# power.net
KiCad netlist of a schematic drawn in Altium Designer
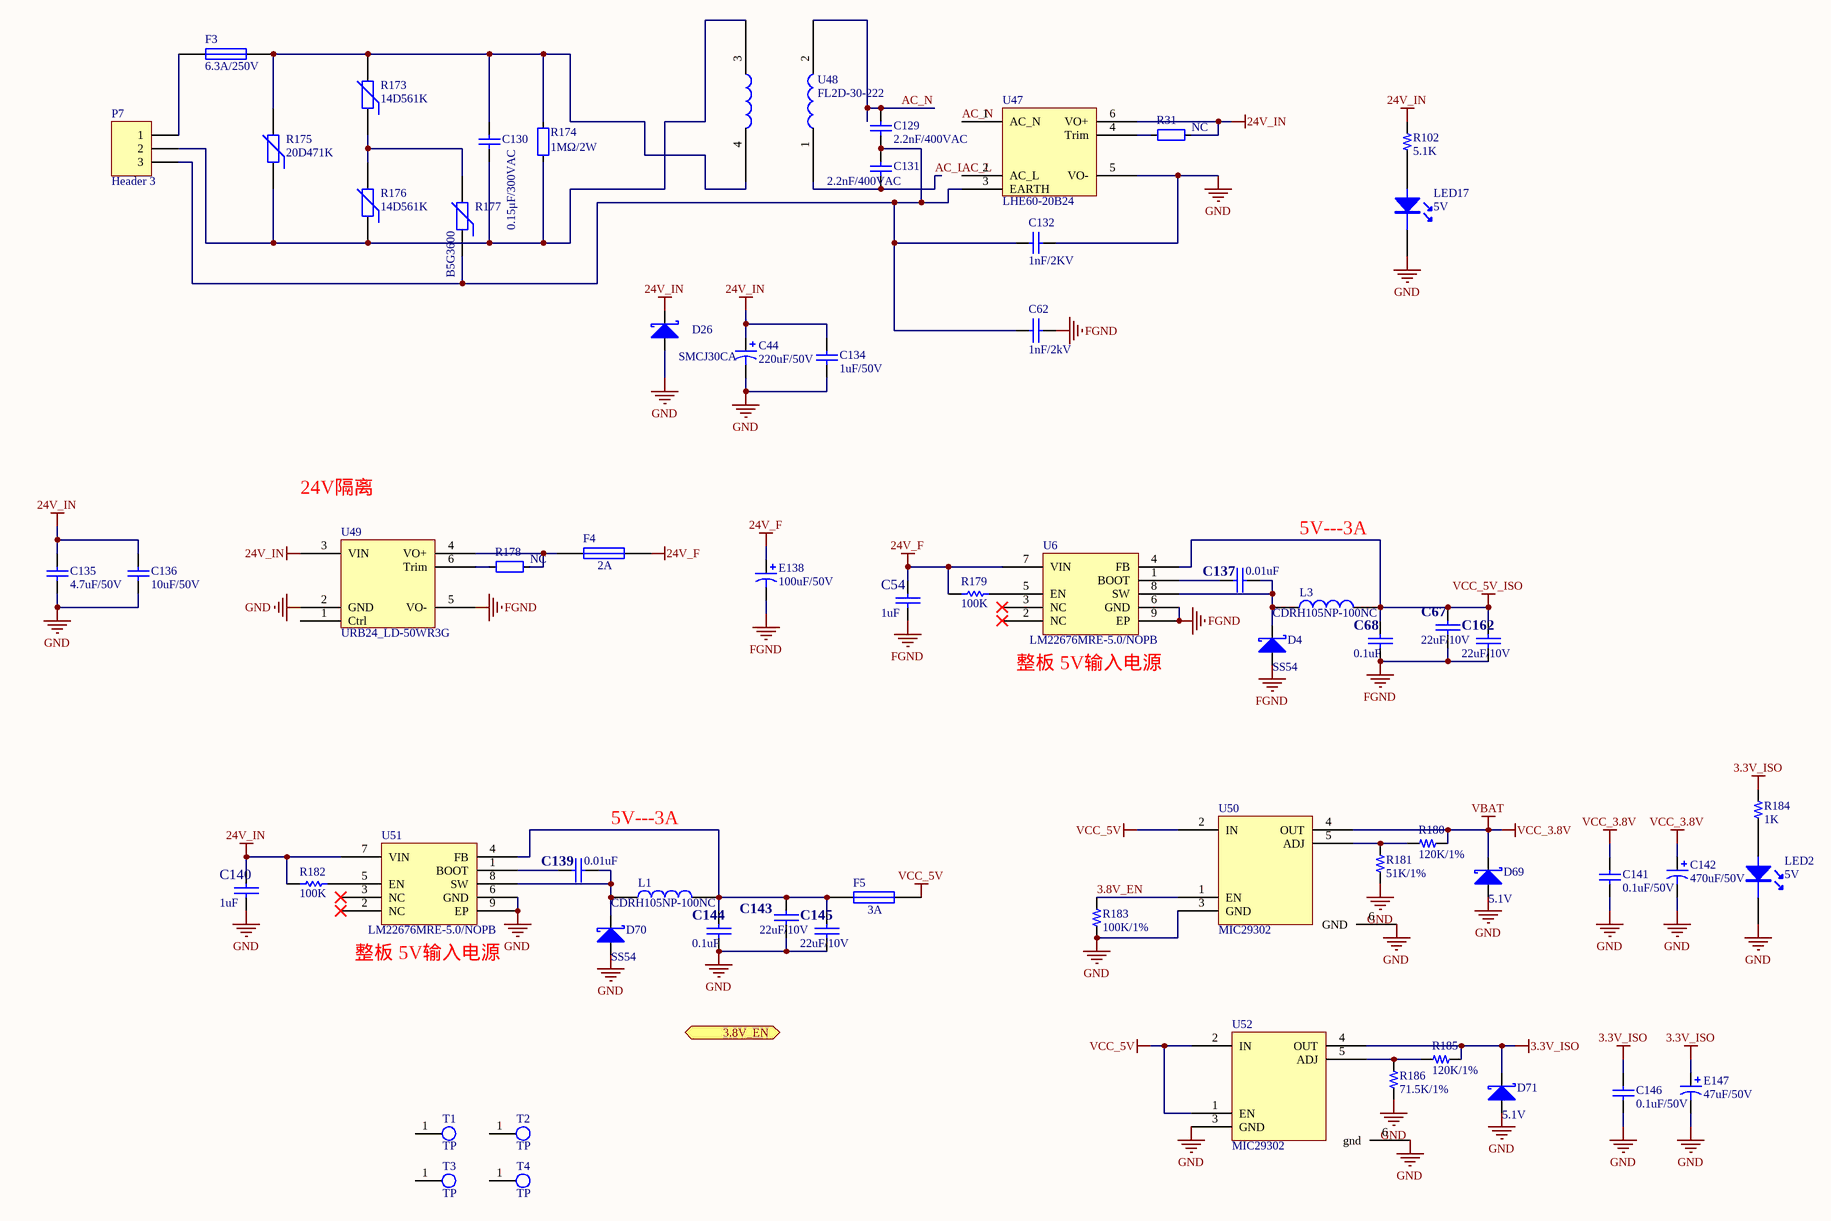
[diagram p0: power.SchDoc]

(export (version "E")
  (design (tool "Eeschema 10.0.6"))
  (components
    (comp (ref "C44")
      (value "220uF/50V")
      (footprint "Φ10×10")
      (description "Polarized Capacitor (Radial)")
      (fields (field (name "PUBLISHER") "Altium Limited"))
      (libsource (lib "Miscellaneous Devices") (part "Cap Pol1"))
    )
    (comp (ref "C54")
      (value "1uF")
      (footprint "0603C")
      (description "Capacitor")
      (libsource (lib "*") (part "CAP"))
    )
    (comp (ref "C62")
      (value "1nF/2kV")
      (footprint "1206C")
      (description "Capacitor")
      (libsource (lib "*") (part "CAP"))
    )
    (comp (ref "C67")
      (value "22uF/10V")
      (footprint "1210C")
      (description "Capacitor")
      (libsource (lib "*") (part "CAP"))
    )
    (comp (ref "C68")
      (value "0.1uF")
      (footprint "0603C")
      (description "Capacitor")
      (libsource (lib "*") (part "CAP"))
    )
    (comp (ref "C129")
      (value "2.2nF/400VAC")
      (footprint "15x18")
      (description "Capacitor")
      (fields (field (name "PUBLISHER") "Altium Limited"))
      (libsource (lib "Miscellaneous Devices") (part "Cap"))
    )
    (comp (ref "C130")
      (value "0.15μF/300VAC")
      (footprint "15x18")
      (description "Capacitor")
      (fields (field (name "PUBLISHER") "Altium Limited"))
      (libsource (lib "Miscellaneous Devices") (part "Cap"))
    )
    (comp (ref "C131")
      (value "2.2nF/400VAC")
      (footprint "15x18")
      (description "Capacitor")
      (fields (field (name "PUBLISHER") "Altium Limited"))
      (libsource (lib "Miscellaneous Devices") (part "Cap"))
    )
    (comp (ref "C132")
      (value "1nF/2KV")
      (footprint "1206C")
      (description "Capacitor")
      (fields (field (name "PUBLISHER") "Altium Limited"))
      (libsource (lib "Miscellaneous Devices") (part "Cap"))
    )
    (comp (ref "C134")
      (value "1uF/50V")
      (footprint "1210C")
      (description "Capacitor")
      (fields (field (name "PUBLISHER") "Altium Limited"))
      (libsource (lib "Miscellaneous Devices") (part "Cap"))
    )
    (comp (ref "C135")
      (value "4.7uF/50V")
      (footprint "1210C")
      (description "Capacitor")
      (fields (field (name "PUBLISHER") "Altium Limited"))
      (libsource (lib "Miscellaneous Devices") (part "Cap"))
    )
    (comp (ref "C136")
      (value "10uF/50V")
      (footprint "1210C")
      (description "Capacitor")
      (fields (field (name "PUBLISHER") "Altium Limited"))
      (libsource (lib "Miscellaneous Devices") (part "Cap"))
    )
    (comp (ref "C137")
      (value "0.01uF")
      (footprint "0603C")
      (description "Capacitor")
      (libsource (lib "*") (part "CAP"))
    )
    (comp (ref "C139")
      (value "0.01uF")
      (footprint "0603C")
      (description "Capacitor")
      (libsource (lib "*") (part "CAP"))
    )
    (comp (ref "C140")
      (value "1uF")
      (footprint "0603C")
      (description "Capacitor")
      (libsource (lib "*") (part "CAP"))
    )
    (comp (ref "C141")
      (value "0.1uF/50V")
      (footprint "0603C")
      (description "Capacitor")
      (fields (field (name "PUBLISHER") "Altium Limited"))
      (libsource (lib "Miscellaneous Devices") (part "Cap"))
    )
    (comp (ref "C142")
      (value "470uF/50V")
      (footprint "Φ10×10")
      (description "Polarized Capacitor (Radial)")
      (fields (field (name "PUBLISHER") "Altium Limited"))
      (libsource (lib "Miscellaneous Devices") (part "Cap Pol1"))
    )
    (comp (ref "C143")
      (value "22uF/10V")
      (footprint "1210C")
      (description "Capacitor")
      (libsource (lib "*") (part "CAP"))
    )
    (comp (ref "C144")
      (value "0.1uF")
      (footprint "0603C")
      (description "Capacitor")
      (libsource (lib "*") (part "CAP"))
    )
    (comp (ref "C145")
      (value "22uF/10V")
      (footprint "1210C")
      (description "Capacitor")
      (libsource (lib "*") (part "CAP"))
    )
    (comp (ref "C146")
      (value "0.1uF/50V")
      (footprint "0603C")
      (description "Capacitor")
      (fields (field (name "PUBLISHER") "Altium Limited"))
      (libsource (lib "Miscellaneous Devices") (part "Cap"))
    )
    (comp (ref "C162")
      (value "22uF/10V")
      (footprint "1210C")
      (description "Capacitor")
      (libsource (lib "*") (part "CAP"))
    )
    (comp (ref "D4")
      (value "SS54")
      (footprint "SMC")
      (description "Schottky Diode")
      (libsource (lib "*") (part "DIODE S"))
    )
    (comp (ref "D26")
      (value "SMCJ30CA")
      (footprint "SMC")
      (description "Schottky Diode")
      (libsource (lib "*") (part "DIODE S"))
    )
    (comp (ref "D69")
      (value "5.1V")
      (footprint "SMA")
      (description "Schottky Diode")
      (libsource (lib "*") (part "DIODE S"))
    )
    (comp (ref "D70")
      (value "SS54")
      (footprint "SMC")
      (description "Schottky Diode")
      (libsource (lib "*") (part "DIODE S"))
    )
    (comp (ref "D71")
      (value "5.1V")
      (footprint "SMA")
      (description "Schottky Diode")
      (libsource (lib "*") (part "DIODE S"))
    )
    (comp (ref "E138")
      (value "100uF/50V")
      (footprint "Φ10×10")
      (description "Polarized Capacitor (Radial)")
      (fields (field (name "PUBLISHER") "Altium Limited"))
      (libsource (lib "Miscellaneous Devices") (part "Cap Pol1"))
    )
    (comp (ref "E147")
      (value "47uF/50V")
      (footprint "Φ10×10")
      (description "Polarized Capacitor (Radial)")
      (fields (field (name "PUBLISHER") "Altium Limited"))
      (libsource (lib "Miscellaneous Devices") (part "Cap Pol1"))
    )
    (comp (ref "F3")
      (value "6.3A/250V")
      (footprint "可视开关电源保险丝座")
      (description "Fuse")
      (fields (field (name "PUBLISHER") "Altium Limited"))
      (libsource (lib "Miscellaneous Devices") (part "Fuse 1"))
    )
    (comp (ref "F4")
      (value "2A")
      (footprint "1812-F")
      (description "Fuse")
      (fields (field (name "PUBLISHER") "Altium Limited"))
      (libsource (lib "Miscellaneous Devices") (part "Fuse 1"))
    )
    (comp (ref "F5")
      (value "3A")
      (footprint "1812-F")
      (description "Fuse")
      (fields (field (name "PUBLISHER") "Altium Limited"))
      (libsource (lib "Miscellaneous Devices") (part "Fuse 1"))
    )
    (comp (ref "L1") (value "CDRH105NP-100NC") (footprint "CDRH105") (libsource (lib "*") (part "INDUCTOR")))
    (comp (ref "L3") (value "CDRH105NP-100NC") (footprint "CDRH105") (libsource (lib "*") (part "INDUCTOR")))
    (comp (ref "LED2") (value "5V") (footprint "0603LED") (libsource (lib "*") (part "LED")))
    (comp (ref "LED17") (value "5V") (footprint "0603LED") (libsource (lib "*") (part "LED")))
    (comp (ref "P7")
      (value "Header 3")
      (footprint "KF128V-3P")
      (description "Header, 3-Pin")
      (fields (field (name "PUBLISHER") "Altium Limited"))
      (libsource (lib "Miscellaneous Connectors") (part "Header 3"))
    )
    (comp (ref "R31") (value "NC") (footprint "0603r") (libsource (lib "RC_M_D_00") (part "RES0603")))
    (comp (ref "R102")
      (value "5.1K")
      (footprint "0603R")
      (description "R")
      (libsource (lib "JRJ_1") (part "R"))
    )
    (comp (ref "R173")
      (value "14D561K")
      (footprint "14D561K")
      (description "Varistor (Voltage-Sensitive Resistor)")
      (fields (field (name "PUBLISHER") "Altium Limited"))
      (libsource (lib "Miscellaneous Devices") (part "Res Varistor"))
    )
    (comp (ref "R174") (value "1MΩ/2W") (footprint "5x15.5") (libsource (lib "RC_M_D_00") (part "RES0603")))
    (comp (ref "R175")
      (value "20D471K")
      (footprint "20D471K")
      (description "Varistor (Voltage-Sensitive Resistor)")
      (fields (field (name "PUBLISHER") "Altium Limited"))
      (libsource (lib "Miscellaneous Devices") (part "Res Varistor"))
    )
    (comp (ref "R176")
      (value "14D561K")
      (footprint "14D561K")
      (description "Varistor (Voltage-Sensitive Resistor)")
      (fields (field (name "PUBLISHER") "Altium Limited"))
      (libsource (lib "Miscellaneous Devices") (part "Res Varistor"))
    )
    (comp (ref "R177")
      (value "B5G3600")
      (footprint "B5G3600")
      (description "Varistor (Voltage-Sensitive Resistor)")
      (fields (field (name "PUBLISHER") "Altium Limited"))
      (libsource (lib "Miscellaneous Devices") (part "Res Varistor"))
    )
    (comp (ref "R178") (value "NC") (footprint "0603r") (libsource (lib "RC_M_D_00") (part "RES0603")))
    (comp (ref "R179")
      (value "100K")
      (footprint "0603R")
      (description "Resistor")
      (fields (field (name "PUBLISHER") "Altium Limited"))
      (libsource (lib "Miscellaneous Devices") (part "Res1"))
    )
    (comp (ref "R180")
      (value "120K/1%")
      (footprint "0603R")
      (description "R")
      (libsource (lib "JRJ_1") (part "R"))
    )
    (comp (ref "R181")
      (value "51K/1%")
      (footprint "0603R")
      (description "R")
      (libsource (lib "JRJ_1") (part "R"))
    )
    (comp (ref "R182")
      (value "100K")
      (footprint "0603R")
      (description "Resistor")
      (fields (field (name "PUBLISHER") "Altium Limited"))
      (libsource (lib "Miscellaneous Devices") (part "Res1"))
    )
    (comp (ref "R183")
      (value "100K/1%")
      (footprint "0603R")
      (description "R")
      (libsource (lib "JRJ_1") (part "R"))
    )
    (comp (ref "R184")
      (value "1K")
      (footprint "0603R")
      (description "R")
      (libsource (lib "JRJ_1") (part "R"))
    )
    (comp (ref "R185")
      (value "120K/1%")
      (footprint "0603R")
      (description "R")
      (libsource (lib "JRJ_1") (part "R"))
    )
    (comp (ref "R186")
      (value "71.5K/1%")
      (footprint "0603R")
      (description "R")
      (libsource (lib "JRJ_1") (part "R"))
    )
    (comp (ref "T1") (value "TP") (footprint "m2.5") (libsource (lib "Schlib_20110825") (part "TP")))
    (comp (ref "T2") (value "TP") (footprint "m2.5") (libsource (lib "Schlib_20110825") (part "TP")))
    (comp (ref "T3") (value "TP") (footprint "m2.5") (libsource (lib "Schlib_20110825") (part "TP")))
    (comp (ref "T4") (value "TP") (footprint "m2.5") (libsource (lib "Schlib_20110825") (part "TP")))
    (comp (ref "U6")
      (value "LM22676MRE-5.0/NOPB")
      (footprint "SOP127P600X168_HS-8N")
      (libsource (lib "Schlib1") (part "LM22676MR-5.0"))
    )
    (comp (ref "U47")
      (value "LHE60-20B24")
      (footprint "LHE60-20B24")
      (libsource (lib "Schlib1") (part "LHE60-20B24"))
    )
    (comp (ref "U48")
      (value "FL2D-30-222")
      (footprint "TY-100P")
      (description "PCB mounting filters")
      (libsource (lib "power") (part "TY-100P"))
    )
    (comp (ref "U49")
      (value "URB24_LD-50WR3G")
      (footprint "URB24_LD-50WR3G")
      (libsource (lib "Schlib1") (part "URB24_LD-50WR3G"))
    )
    (comp (ref "U50")
      (value "MIC29302")
      (footprint "TO228P1435X457-6N")
      (libsource (lib "power") (part "MIC29302"))
    )
    (comp (ref "U51")
      (value "LM22676MRE-5.0/NOPB")
      (footprint "SOP127P600X168_HS-8N")
      (libsource (lib "Schlib1") (part "LM22676MR-5.0"))
    )
    (comp (ref "U52")
      (value "MIC29302")
      (footprint "TO228P1435X457-6N")
      (libsource (lib "power") (part "MIC29302"))
    )
  )
  (nets
    (net (code "1") (name "/3.8V_EN") (class "Default")
      (node (ref "R183") (pin "2") (pintype "passive"))
      (node (ref "U50") (pin "1") (pinfunction "EN_1") (pintype "passive"))
    )
    (net (code "2") (name "/AC_L") (class "Default")
      (node (ref "C131") (pin "1") (pinfunction "1_1") (pintype "passive"))
      (node (ref "U47") (pin "2") (pinfunction "AC_L_2") (pintype "passive"))
      (node (ref "U48") (pin "1") (pinfunction "L_1") (pintype "passive"))
    )
    (net (code "3") (name "/AC_N") (class "Default")
      (node (ref "C129") (pin "2") (pinfunction "2_2") (pintype "passive"))
      (node (ref "U47") (pin "1") (pinfunction "AC_N_1") (pintype "passive"))
      (node (ref "U48") (pin "2") (pinfunction "L_2") (pintype "passive"))
    )
    (net (code "4") (name "3.3V_ISO") (class "Default")
      (node (ref "C146") (pin "2") (pinfunction "2_2") (pintype "passive"))
      (node (ref "D71") (pin "2") (pinfunction "K_2") (pintype "passive"))
      (node (ref "E147") (pin "1") (pinfunction "1_1") (pintype "passive"))
      (node (ref "R184") (pin "2") (pintype "passive"))
      (node (ref "R185") (pin "1") (pintype "passive"))
      (node (ref "U52") (pin "4") (pinfunction "OUT_4") (pintype "passive"))
    )
    (net (code "5") (name "24V_F") (class "Default")
      (node (ref "C54") (pin "2") (pinfunction "2_2") (pintype "passive"))
      (node (ref "E138") (pin "1") (pinfunction "1_1") (pintype "passive"))
      (node (ref "F4") (pin "2") (pinfunction "2_2") (pintype "passive"))
      (node (ref "R179") (pin "2") (pinfunction "2_2") (pintype "passive"))
      (node (ref "U6") (pin "7") (pinfunction "VIN_7") (pintype "passive"))
    )
    (net (code "6") (name "24V_IN") (class "Default")
      (node (ref "C134") (pin "2") (pinfunction "2_2") (pintype "passive"))
      (node (ref "C135") (pin "2") (pinfunction "2_2") (pintype "passive"))
      (node (ref "C136") (pin "2") (pinfunction "2_2") (pintype "passive"))
      (node (ref "C140") (pin "2") (pinfunction "2_2") (pintype "passive"))
      (node (ref "C44") (pin "1") (pinfunction "1_1") (pintype "passive"))
      (node (ref "D26") (pin "2") (pinfunction "K_2") (pintype "passive"))
      (node (ref "R102") (pin "2") (pintype "passive"))
      (node (ref "R182") (pin "2") (pinfunction "2_2") (pintype "passive"))
      (node (ref "R31") (pin "2") (pinfunction "2_2") (pintype "passive"))
      (node (ref "U47") (pin "6") (pinfunction "VO+_6") (pintype "passive"))
      (node (ref "U49") (pin "3") (pinfunction "VIN_3") (pintype "passive"))
      (node (ref "U51") (pin "7") (pinfunction "VIN_7") (pintype "passive"))
    )
    (net (code "7") (name "FGND") (class "Default")
      (node (ref "C162") (pin "2") (pinfunction "2_2") (pintype "passive"))
      (node (ref "C54") (pin "1") (pinfunction "1_1") (pintype "passive"))
      (node (ref "C62") (pin "1") (pinfunction "1_1") (pintype "passive"))
      (node (ref "C67") (pin "2") (pinfunction "2_2") (pintype "passive"))
      (node (ref "C68") (pin "2") (pinfunction "2_2") (pintype "passive"))
      (node (ref "D4") (pin "1") (pinfunction "A_1") (pintype "passive"))
      (node (ref "E138") (pin "2") (pinfunction "2_2") (pintype "passive"))
      (node (ref "U49") (pin "5") (pinfunction "VO-_5") (pintype "passive"))
      (node (ref "U6") (pin "6") (pinfunction "GND_6") (pintype "passive"))
      (node (ref "U6") (pin "9") (pinfunction "EP_9") (pintype "passive"))
    )
    (net (code "8") (name "GND") (class "Default")
      (node (ref "C132") (pin "1") (pinfunction "1_1") (pintype "passive"))
      (node (ref "C134") (pin "1") (pinfunction "1_1") (pintype "passive"))
      (node (ref "C135") (pin "1") (pinfunction "1_1") (pintype "passive"))
      (node (ref "C136") (pin "1") (pinfunction "1_1") (pintype "passive"))
      (node (ref "C140") (pin "1") (pinfunction "1_1") (pintype "passive"))
      (node (ref "C141") (pin "1") (pinfunction "1_1") (pintype "passive"))
      (node (ref "C142") (pin "2") (pinfunction "2_2") (pintype "passive"))
      (node (ref "C143") (pin "2") (pinfunction "2_2") (pintype "passive"))
      (node (ref "C144") (pin "2") (pinfunction "2_2") (pintype "passive"))
      (node (ref "C145") (pin "2") (pinfunction "2_2") (pintype "passive"))
      (node (ref "C146") (pin "1") (pinfunction "1_1") (pintype "passive"))
      (node (ref "C44") (pin "2") (pinfunction "2_2") (pintype "passive"))
      (node (ref "D26") (pin "1") (pinfunction "A_1") (pintype "passive"))
      (node (ref "D69") (pin "1") (pinfunction "A_1") (pintype "passive"))
      (node (ref "D70") (pin "1") (pinfunction "A_1") (pintype "passive"))
      (node (ref "D71") (pin "1") (pinfunction "A_1") (pintype "passive"))
      (node (ref "E147") (pin "2") (pinfunction "2_2") (pintype "passive"))
      (node (ref "LED17") (pin "2") (pinfunction "2_2") (pintype "passive"))
      (node (ref "LED2") (pin "2") (pinfunction "2_2") (pintype "passive"))
      (node (ref "R181") (pin "1") (pintype "passive"))
      (node (ref "R183") (pin "1") (pintype "passive"))
      (node (ref "R186") (pin "1") (pintype "passive"))
      (node (ref "U47") (pin "5") (pinfunction "VO-_5") (pintype "passive"))
      (node (ref "U49") (pin "2") (pinfunction "GND_2") (pintype "passive"))
      (node (ref "U50") (pin "3") (pinfunction "GND_3") (pintype "passive"))
      (node (ref "U50") (pin "6") (pinfunction "gnd_6") (pintype "passive"))
      (node (ref "U51") (pin "6") (pinfunction "GND_6") (pintype "passive"))
      (node (ref "U51") (pin "9") (pinfunction "EP_9") (pintype "passive"))
      (node (ref "U52") (pin "3") (pinfunction "GND_3") (pintype "passive"))
      (node (ref "U52") (pin "6") (pinfunction "gnd_6") (pintype "passive"))
    )
    (net (code "9") (name "Net-(C130-Pad1)") (class "Default")
      (node (ref "C130") (pin "1") (pinfunction "1_1") (pintype "passive"))
      (node (ref "P7") (pin "2") (pinfunction "2_2") (pintype "passive"))
      (node (ref "R174") (pin "2") (pinfunction "2_2") (pintype "passive"))
      (node (ref "R175") (pin "1") (pinfunction "1_1") (pintype "passive"))
      (node (ref "R176") (pin "1") (pinfunction "1_1") (pintype "passive"))
      (node (ref "U48") (pin "3") (pinfunction "L_3") (pintype "passive"))
    )
    (net (code "10") (name "Net-(C130-Pad2)") (class "Default")
      (node (ref "C130") (pin "2") (pinfunction "2_2") (pintype "passive"))
      (node (ref "F3") (pin "2") (pinfunction "2_2") (pintype "passive"))
      (node (ref "R173") (pin "2") (pinfunction "2_2") (pintype "passive"))
      (node (ref "R174") (pin "1") (pinfunction "1_1") (pintype "passive"))
      (node (ref "R175") (pin "2") (pinfunction "2_2") (pintype "passive"))
      (node (ref "U48") (pin "4") (pintype "passive"))
    )
    (net (code "11") (name "Net-(D4-K)") (class "Default")
      (node (ref "C137") (pin "1") (pinfunction "1_1") (pintype "passive"))
      (node (ref "D4") (pin "2") (pinfunction "K_2") (pintype "passive"))
      (node (ref "L3") (pin "1") (pinfunction "1_1") (pintype "passive"))
      (node (ref "U6") (pin "8") (pinfunction "SW_8") (pintype "passive"))
    )
    (net (code "12") (name "Net-(D70-K)") (class "Default")
      (node (ref "C139") (pin "1") (pinfunction "1_1") (pintype "passive"))
      (node (ref "D70") (pin "2") (pinfunction "K_2") (pintype "passive"))
      (node (ref "L1") (pin "1") (pinfunction "1_1") (pintype "passive"))
      (node (ref "U51") (pin "8") (pinfunction "SW_8") (pintype "passive"))
    )
    (net (code "13") (name "Net-(F3-Pad1)") (class "Default")
      (node (ref "F3") (pin "1") (pinfunction "1_1") (pintype "passive"))
      (node (ref "P7") (pin "1") (pinfunction "1_1") (pintype "passive"))
    )
    (net (code "14") (name "Net-(LED2-Pad1)") (class "Default")
      (node (ref "LED2") (pin "1") (pinfunction "1_1") (pintype "passive"))
      (node (ref "R184") (pin "1") (pintype "passive"))
    )
    (net (code "15") (name "Net-(LED17-Pad1)") (class "Default")
      (node (ref "LED17") (pin "1") (pinfunction "1_1") (pintype "passive"))
      (node (ref "R102") (pin "1") (pintype "passive"))
    )
    (net (code "16") (name "Net-(R173-Pad1)") (class "Default")
      (node (ref "R173") (pin "1") (pinfunction "1_1") (pintype "passive"))
      (node (ref "R176") (pin "2") (pinfunction "2_2") (pintype "passive"))
      (node (ref "R177") (pin "2") (pinfunction "2_2") (pintype "passive"))
    )
    (net (code "17") (name "Net-(U6-BOOT)") (class "Default")
      (node (ref "C137") (pin "2") (pinfunction "2_2") (pintype "passive"))
      (node (ref "U6") (pin "1") (pinfunction "BOOT_1") (pintype "passive"))
    )
    (net (code "18") (name "Net-(U6-EN)") (class "Default")
      (node (ref "R179") (pin "1") (pinfunction "1_1") (pintype "passive"))
      (node (ref "U6") (pin "5") (pinfunction "EN_5") (pintype "passive"))
    )
    (net (code "19") (name "Net-(U47-EARTH)") (class "Default")
      (node (ref "C129") (pin "1") (pinfunction "1_1") (pintype "passive"))
      (node (ref "C131") (pin "2") (pinfunction "2_2") (pintype "passive"))
      (node (ref "C132") (pin "2") (pinfunction "2_2") (pintype "passive"))
      (node (ref "C62") (pin "2") (pinfunction "2_2") (pintype "passive"))
      (node (ref "P7") (pin "3") (pinfunction "3_3") (pintype "passive"))
      (node (ref "R177") (pin "1") (pinfunction "1_1") (pintype "passive"))
      (node (ref "U47") (pin "3") (pinfunction "EARTH_3") (pintype "passive"))
    )
    (net (code "20") (name "Net-(U47-Trim)") (class "Default")
      (node (ref "R31") (pin "1") (pinfunction "1_1") (pintype "passive"))
      (node (ref "U47") (pin "4") (pinfunction "Trim_4") (pintype "passive"))
    )
    (net (code "21") (name "Net-(U49-Trim)") (class "Default")
      (node (ref "R178") (pin "1") (pinfunction "1_1") (pintype "passive"))
      (node (ref "U49") (pin "6") (pinfunction "Trim_6") (pintype "passive"))
    )
    (net (code "22") (name "Net-(U49-VO+)") (class "Default")
      (node (ref "F4") (pin "1") (pinfunction "1_1") (pintype "passive"))
      (node (ref "R178") (pin "2") (pinfunction "2_2") (pintype "passive"))
      (node (ref "U49") (pin "4") (pinfunction "VO+_4") (pintype "passive"))
    )
    (net (code "23") (name "Net-(U50-ADJ)") (class "Default")
      (node (ref "R180") (pin "2") (pintype "passive"))
      (node (ref "R181") (pin "2") (pintype "passive"))
      (node (ref "U50") (pin "5") (pinfunction "ADJ_5") (pintype "passive"))
    )
    (net (code "24") (name "Net-(U51-BOOT)") (class "Default")
      (node (ref "C139") (pin "2") (pinfunction "2_2") (pintype "passive"))
      (node (ref "U51") (pin "1") (pinfunction "BOOT_1") (pintype "passive"))
    )
    (net (code "25") (name "Net-(U51-EN)") (class "Default")
      (node (ref "R182") (pin "1") (pinfunction "1_1") (pintype "passive"))
      (node (ref "U51") (pin "5") (pinfunction "EN_5") (pintype "passive"))
    )
    (net (code "26") (name "Net-(U51-FB)") (class "Default")
      (node (ref "C143") (pin "1") (pinfunction "1_1") (pintype "passive"))
      (node (ref "C144") (pin "1") (pinfunction "1_1") (pintype "passive"))
      (node (ref "C145") (pin "1") (pinfunction "1_1") (pintype "passive"))
      (node (ref "F5") (pin "1") (pinfunction "1_1") (pintype "passive"))
      (node (ref "L1") (pin "2") (pinfunction "2_2") (pintype "passive"))
      (node (ref "U51") (pin "4") (pinfunction "FB_4") (pintype "passive"))
    )
    (net (code "27") (name "Net-(U52-ADJ)") (class "Default")
      (node (ref "R185") (pin "2") (pintype "passive"))
      (node (ref "R186") (pin "2") (pintype "passive"))
      (node (ref "U52") (pin "5") (pinfunction "ADJ_5") (pintype "passive"))
    )
    (net (code "28") (name "VBAT") (class "Default")
      (node (ref "C141") (pin "2") (pinfunction "2_2") (pintype "passive"))
      (node (ref "C142") (pin "1") (pinfunction "1_1") (pintype "passive"))
      (node (ref "D69") (pin "2") (pinfunction "K_2") (pintype "passive"))
      (node (ref "R180") (pin "1") (pintype "passive"))
      (node (ref "U50") (pin "4") (pinfunction "OUT_4") (pintype "passive"))
    )
    (net (code "29") (name "VCC_5V") (class "Default")
      (node (ref "F5") (pin "2") (pinfunction "2_2") (pintype "passive"))
      (node (ref "U50") (pin "2") (pinfunction "IN_2") (pintype "passive"))
      (node (ref "U52") (pin "1") (pinfunction "EN_1") (pintype "passive"))
      (node (ref "U52") (pin "2") (pinfunction "IN_2") (pintype "passive"))
    )
    (net (code "30") (name "VCC_5V_ISO") (class "Default")
      (node (ref "C162") (pin "1") (pinfunction "1_1") (pintype "passive"))
      (node (ref "C67") (pin "1") (pinfunction "1_1") (pintype "passive"))
      (node (ref "C68") (pin "1") (pinfunction "1_1") (pintype "passive"))
      (node (ref "L3") (pin "2") (pinfunction "2_2") (pintype "passive"))
      (node (ref "U6") (pin "4") (pinfunction "FB_4") (pintype "passive"))
    )
    (net (code "31") (name "unconnected-(T1-Pad1)") (class "Default")
      (node (ref "T1") (pin "1") (pintype "passive"))
    )
    (net (code "32") (name "unconnected-(T2-Pad1)") (class "Default")
      (node (ref "T2") (pin "1") (pintype "passive"))
    )
    (net (code "33") (name "unconnected-(T3-Pad1)") (class "Default")
      (node (ref "T3") (pin "1") (pintype "passive"))
    )
    (net (code "34") (name "unconnected-(T4-Pad1)") (class "Default")
      (node (ref "T4") (pin "1") (pintype "passive"))
    )
    (net (code "35") (name "unconnected-(U6-NC-Pad2)") (class "Default")
      (node (ref "U6") (pin "2") (pinfunction "NC_2") (pintype "passive+no_connect"))
    )
    (net (code "36") (name "unconnected-(U6-NC-Pad3)") (class "Default")
      (node (ref "U6") (pin "3") (pinfunction "NC_3") (pintype "passive+no_connect"))
    )
    (net (code "37") (name "unconnected-(U49-Ctrl-Pad1)") (class "Default")
      (node (ref "U49") (pin "1") (pinfunction "Ctrl_1") (pintype "passive"))
    )
    (net (code "38") (name "unconnected-(U51-NC-Pad2)") (class "Default")
      (node (ref "U51") (pin "2") (pinfunction "NC_2") (pintype "passive+no_connect"))
    )
    (net (code "39") (name "unconnected-(U51-NC-Pad3)") (class "Default")
      (node (ref "U51") (pin "3") (pinfunction "NC_3") (pintype "passive+no_connect"))
    )
  )
)
